# x-OSC_Gloves_v4_2.net
KiCad netlist of a schematic drawn in EAGLE
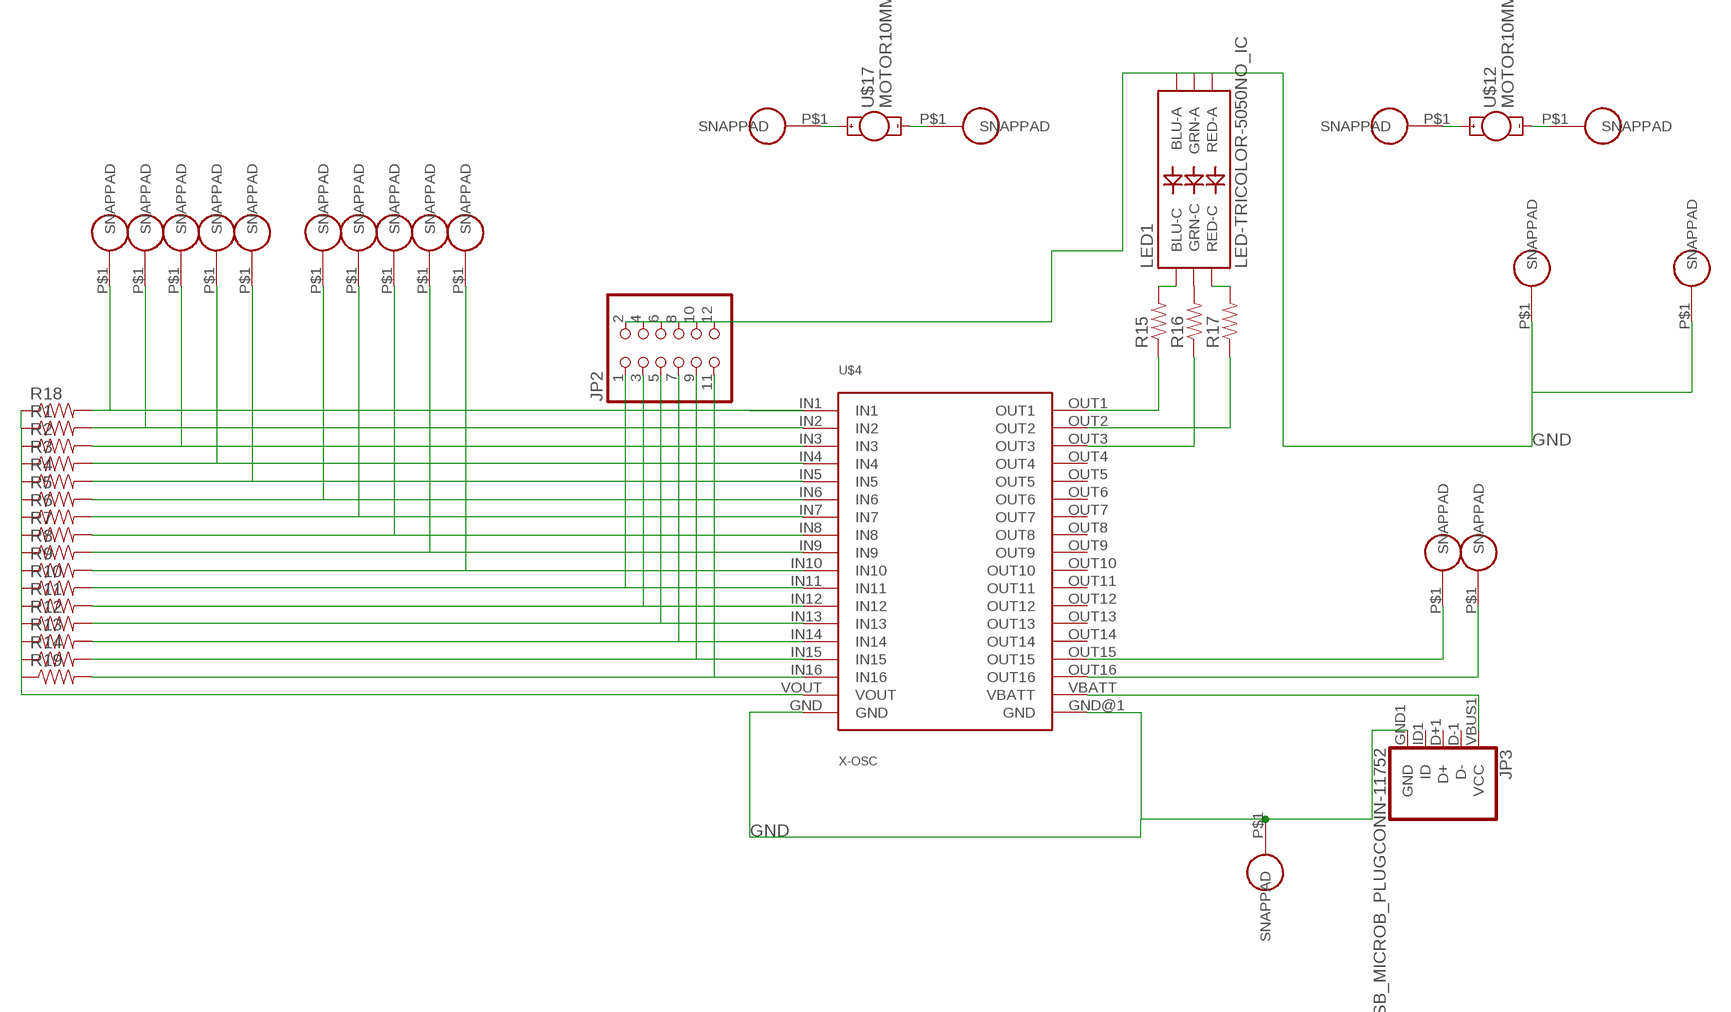
[diagram p0: schematic, sheet 1]

(export (version "E")
  (design (tool "Eeschema 10.0.6"))
  (components
    (comp (ref "JP2")
      (value "PINHD-2X6/90")
      (footprint "eagle-import:2X06_90")
      (libsource (lib "eagle-import") (part "PINHD-2X6/90"))
    )
    (comp (ref "JP3")
      (value "USB_MICROB_PLUGCONN-11752")
      (footprint "eagle-import:USB-B-MICRO-SMD_V03")
      (libsource (lib "eagle-import") (part "USB_MICROB_PLUGCONN-11752"))
    )
    (comp (ref "LED1")
      (value "LED-TRICOLOR-5050NO_IC")
      (footprint "eagle-import:LED-TRICOLOR-5050")
      (libsource (lib "eagle-import") (part "LED-TRICOLOR-5050NO_IC"))
    )
    (comp (ref "R1")
      (value "RESISTOR0805-RES")
      (footprint "eagle-import:0805")
      (libsource (lib "eagle-import") (part "RESISTOR0805-RES"))
    )
    (comp (ref "R2")
      (value "RESISTOR0805-RES")
      (footprint "eagle-import:0805")
      (libsource (lib "eagle-import") (part "RESISTOR0805-RES"))
    )
    (comp (ref "R3")
      (value "RESISTOR0805-RES")
      (footprint "eagle-import:0805")
      (libsource (lib "eagle-import") (part "RESISTOR0805-RES"))
    )
    (comp (ref "R4")
      (value "RESISTOR0805-RES")
      (footprint "eagle-import:0805")
      (libsource (lib "eagle-import") (part "RESISTOR0805-RES"))
    )
    (comp (ref "R5")
      (value "RESISTOR0805-RES")
      (footprint "eagle-import:0805")
      (libsource (lib "eagle-import") (part "RESISTOR0805-RES"))
    )
    (comp (ref "R6")
      (value "RESISTOR0805-RES")
      (footprint "eagle-import:0805")
      (libsource (lib "eagle-import") (part "RESISTOR0805-RES"))
    )
    (comp (ref "R7")
      (value "RESISTOR0805-RES")
      (footprint "eagle-import:0805")
      (libsource (lib "eagle-import") (part "RESISTOR0805-RES"))
    )
    (comp (ref "R8")
      (value "RESISTOR0805-RES")
      (footprint "eagle-import:0805")
      (libsource (lib "eagle-import") (part "RESISTOR0805-RES"))
    )
    (comp (ref "R9")
      (value "RESISTOR0805-RES")
      (footprint "eagle-import:0805")
      (libsource (lib "eagle-import") (part "RESISTOR0805-RES"))
    )
    (comp (ref "R10")
      (value "RESISTOR0805-RES")
      (footprint "eagle-import:0805")
      (libsource (lib "eagle-import") (part "RESISTOR0805-RES"))
    )
    (comp (ref "R11")
      (value "RESISTOR0805-RES")
      (footprint "eagle-import:0805")
      (libsource (lib "eagle-import") (part "RESISTOR0805-RES"))
    )
    (comp (ref "R12")
      (value "RESISTOR0805-RES")
      (footprint "eagle-import:0805")
      (libsource (lib "eagle-import") (part "RESISTOR0805-RES"))
    )
    (comp (ref "R13")
      (value "RESISTOR0805-RES")
      (footprint "eagle-import:0805")
      (libsource (lib "eagle-import") (part "RESISTOR0805-RES"))
    )
    (comp (ref "R14")
      (value "RESISTOR0805-RES")
      (footprint "eagle-import:0805")
      (libsource (lib "eagle-import") (part "RESISTOR0805-RES"))
    )
    (comp (ref "R15")
      (value "RESISTOR0805-RES")
      (footprint "eagle-import:0805")
      (libsource (lib "eagle-import") (part "RESISTOR0805-RES"))
    )
    (comp (ref "R16")
      (value "RESISTOR0805-RES")
      (footprint "eagle-import:0805")
      (libsource (lib "eagle-import") (part "RESISTOR0805-RES"))
    )
    (comp (ref "R17")
      (value "RESISTOR0805-RES")
      (footprint "eagle-import:0805")
      (libsource (lib "eagle-import") (part "RESISTOR0805-RES"))
    )
    (comp (ref "R18")
      (value "RESISTOR0805-RES")
      (footprint "eagle-import:0805")
      (libsource (lib "eagle-import") (part "RESISTOR0805-RES"))
    )
    (comp (ref "R19")
      (value "RESISTOR0805-RES")
      (footprint "eagle-import:0805")
      (libsource (lib "eagle-import") (part "RESISTOR0805-RES"))
    )
    (comp (ref "U$1")
      (value "SNAP-PAD_7MM_ROUND")
      (footprint "eagle-import:SNAP-PAD_7MM_RD")
      (libsource (lib "eagle-import") (part "SNAP-PAD_7MM_ROUND"))
    )
    (comp (ref "U$2")
      (value "SNAP-PAD_7MM_ROUND")
      (footprint "eagle-import:SNAP-PAD_7MM_RD")
      (libsource (lib "eagle-import") (part "SNAP-PAD_7MM_ROUND"))
    )
    (comp (ref "U$3")
      (value "SNAP-PAD_7MM_ROUND")
      (footprint "eagle-import:SNAP-PAD_7MM_RD")
      (libsource (lib "eagle-import") (part "SNAP-PAD_7MM_ROUND"))
    )
    (comp (ref "U$4")
      (value "X-OSC")
      (footprint "eagle-import:X-OSC_SMD")
      (libsource (lib "eagle-import") (part "X-OSC"))
    )
    (comp (ref "U$6")
      (value "SNAP-PAD_7MM_ROUND")
      (footprint "eagle-import:SNAP-PAD_7MM_RD")
      (libsource (lib "eagle-import") (part "SNAP-PAD_7MM_ROUND"))
    )
    (comp (ref "U$7")
      (value "SNAP-PAD_7MM_ROUND")
      (footprint "eagle-import:SNAP-PAD_7MM_RD")
      (libsource (lib "eagle-import") (part "SNAP-PAD_7MM_ROUND"))
    )
    (comp (ref "U$8")
      (value "SNAP-PAD_7MM_ROUND")
      (footprint "eagle-import:SNAP-PAD_7MM_RD")
      (libsource (lib "eagle-import") (part "SNAP-PAD_7MM_ROUND"))
    )
    (comp (ref "U$9")
      (value "SNAP-PAD_7MM_ROUND")
      (footprint "eagle-import:SNAP-PAD_7MM_RD")
      (libsource (lib "eagle-import") (part "SNAP-PAD_7MM_ROUND"))
    )
    (comp (ref "U$10")
      (value "SNAP-PAD_7MM_ROUND")
      (footprint "eagle-import:SNAP-PAD_7MM_RD")
      (libsource (lib "eagle-import") (part "SNAP-PAD_7MM_ROUND"))
    )
    (comp (ref "U$11")
      (value "SNAP-PAD_7MM_ROUND")
      (footprint "eagle-import:SNAP-PAD_7MM_RD")
      (libsource (lib "eagle-import") (part "SNAP-PAD_7MM_ROUND"))
    )
    (comp (ref "U$12")
      (value "MOTOR10MM")
      (footprint "eagle-import:VIBE-MOTOR-10MM")
      (libsource (lib "eagle-import") (part "MOTOR10MM"))
    )
    (comp (ref "U$13")
      (value "SNAP-PAD_7MM_ROUND")
      (footprint "eagle-import:SNAP-PAD_7MM_RD")
      (libsource (lib "eagle-import") (part "SNAP-PAD_7MM_ROUND"))
    )
    (comp (ref "U$14")
      (value "SNAP-PAD_7MM_ROUND")
      (footprint "eagle-import:SNAP-PAD_7MM_RD")
      (libsource (lib "eagle-import") (part "SNAP-PAD_7MM_ROUND"))
    )
    (comp (ref "U$15")
      (value "SNAP-PAD_7MM_ROUND")
      (footprint "eagle-import:SNAP-PAD_7MM_RD")
      (libsource (lib "eagle-import") (part "SNAP-PAD_7MM_ROUND"))
    )
    (comp (ref "U$16")
      (value "SNAP-PAD_7MM_ROUND")
      (footprint "eagle-import:SNAP-PAD_7MM_RD")
      (libsource (lib "eagle-import") (part "SNAP-PAD_7MM_ROUND"))
    )
    (comp (ref "U$17")
      (value "MOTOR10MM")
      (footprint "eagle-import:VIBE-MOTOR-10MM")
      (libsource (lib "eagle-import") (part "MOTOR10MM"))
    )
    (comp (ref "U$18")
      (value "SNAP-PAD_7MM_ROUND")
      (footprint "eagle-import:SNAP-PAD_7MM_RD")
      (libsource (lib "eagle-import") (part "SNAP-PAD_7MM_ROUND"))
    )
    (comp (ref "U$19")
      (value "SNAP-PAD_7MM_ROUND")
      (footprint "eagle-import:SNAP-PAD_7MM_RD")
      (libsource (lib "eagle-import") (part "SNAP-PAD_7MM_ROUND"))
    )
    (comp (ref "U$20")
      (value "SNAP-PAD_7MM_ROUND")
      (footprint "eagle-import:SNAP-PAD_7MM_RD")
      (libsource (lib "eagle-import") (part "SNAP-PAD_7MM_ROUND"))
    )
    (comp (ref "U$21")
      (value "SNAP-PAD_7MM_ROUND")
      (footprint "eagle-import:SNAP-PAD_7MM_RD")
      (libsource (lib "eagle-import") (part "SNAP-PAD_7MM_ROUND"))
    )
    (comp (ref "U$22")
      (value "SNAP-PAD_7MM_ROUND")
      (footprint "eagle-import:SNAP-PAD_7MM_RD")
      (libsource (lib "eagle-import") (part "SNAP-PAD_7MM_ROUND"))
    )
    (comp (ref "U$23")
      (value "SNAP-PAD_7MM_ROUND")
      (footprint "eagle-import:SNAP-PAD_7MM_RD")
      (libsource (lib "eagle-import") (part "SNAP-PAD_7MM_ROUND"))
    )
  )
  (nets
    (net (code "1") (name "/GND") (class "Default")
      (node (ref "JP2") (pin "10") (pinfunction "10_10") (pintype "passive"))
      (node (ref "JP2") (pin "12") (pinfunction "12_12") (pintype "passive"))
      (node (ref "JP2") (pin "2") (pinfunction "2_2") (pintype "passive"))
      (node (ref "JP2") (pin "4") (pinfunction "4_4") (pintype "passive"))
      (node (ref "JP2") (pin "6") (pinfunction "6_6") (pintype "passive"))
      (node (ref "JP2") (pin "8") (pinfunction "8_8") (pintype "passive"))
      (node (ref "JP3") (pin "GND1") (pinfunction "GND_GND1") (pintype "bidirectional"))
      (node (ref "LED1") (pin "1") (pinfunction "GRN-A_1") (pintype "bidirectional"))
      (node (ref "LED1") (pin "2") (pinfunction "RED-A_2") (pintype "bidirectional"))
      (node (ref "LED1") (pin "3") (pinfunction "BLU-A_3") (pintype "bidirectional"))
      (node (ref "U$15") (pin "P$1") (pinfunction "SNAPPAD_P$1") (pintype "bidirectional"))
      (node (ref "U$16") (pin "P$1") (pinfunction "SNAPPAD_P$1") (pintype "bidirectional"))
      (node (ref "U$18") (pin "P$1") (pinfunction "SNAPPAD_P$1") (pintype "bidirectional"))
      (node (ref "U$4") (pin "GND") (pinfunction "GND_GND") (pintype "bidirectional"))
      (node (ref "U$4") (pin "GND@1") (pinfunction "GND_GND@1") (pintype "bidirectional"))
    )
    (net (code "2") (name "Net-(JP2-Pad1)") (class "Default")
      (node (ref "JP2") (pin "1") (pinfunction "1_1") (pintype "passive"))
      (node (ref "R10") (pin "2") (pinfunction "2_2") (pintype "passive"))
      (node (ref "U$4") (pin "IN11") (pinfunction "IN11_IN11") (pintype "bidirectional"))
    )
    (net (code "3") (name "Net-(JP2-Pad3)") (class "Default")
      (node (ref "JP2") (pin "3") (pinfunction "3_3") (pintype "passive"))
      (node (ref "R11") (pin "2") (pinfunction "2_2") (pintype "passive"))
      (node (ref "U$4") (pin "IN12") (pinfunction "IN12_IN12") (pintype "bidirectional"))
    )
    (net (code "4") (name "Net-(JP2-Pad5)") (class "Default")
      (node (ref "JP2") (pin "5") (pinfunction "5_5") (pintype "passive"))
      (node (ref "R12") (pin "2") (pinfunction "2_2") (pintype "passive"))
      (node (ref "U$4") (pin "IN13") (pinfunction "IN13_IN13") (pintype "bidirectional"))
    )
    (net (code "5") (name "Net-(JP2-Pad7)") (class "Default")
      (node (ref "JP2") (pin "7") (pinfunction "7_7") (pintype "passive"))
      (node (ref "R13") (pin "2") (pinfunction "2_2") (pintype "passive"))
      (node (ref "U$4") (pin "IN14") (pinfunction "IN14_IN14") (pintype "bidirectional"))
    )
    (net (code "6") (name "Net-(JP2-Pad9)") (class "Default")
      (node (ref "JP2") (pin "9") (pinfunction "9_9") (pintype "passive"))
      (node (ref "R14") (pin "2") (pinfunction "2_2") (pintype "passive"))
      (node (ref "U$4") (pin "IN15") (pinfunction "IN15_IN15") (pintype "bidirectional"))
    )
    (net (code "7") (name "Net-(JP2-Pad11)") (class "Default")
      (node (ref "JP2") (pin "11") (pinfunction "11_11") (pintype "passive"))
      (node (ref "R19") (pin "2") (pinfunction "2_2") (pintype "passive"))
      (node (ref "U$4") (pin "IN16") (pinfunction "IN16_IN16") (pintype "bidirectional"))
    )
    (net (code "8") (name "Net-(JP3-VCC)") (class "Default")
      (node (ref "JP3") (pin "VBUS1") (pinfunction "VCC_VBUS1") (pintype "bidirectional"))
      (node (ref "U$4") (pin "VBATT") (pinfunction "VBATT_VBATT") (pintype "bidirectional"))
    )
    (net (code "9") (name "Net-(LED1-BLU-C)") (class "Default")
      (node (ref "LED1") (pin "4") (pinfunction "BLU-C_4") (pintype "bidirectional"))
      (node (ref "R15") (pin "2") (pinfunction "2_2") (pintype "passive"))
    )
    (net (code "10") (name "Net-(LED1-GRN-C)") (class "Default")
      (node (ref "LED1") (pin "6") (pinfunction "GRN-C_6") (pintype "bidirectional"))
      (node (ref "R16") (pin "2") (pinfunction "2_2") (pintype "passive"))
    )
    (net (code "11") (name "Net-(LED1-RED-C)") (class "Default")
      (node (ref "LED1") (pin "5") (pinfunction "RED-C_5") (pintype "bidirectional"))
      (node (ref "R17") (pin "2") (pinfunction "2_2") (pintype "passive"))
    )
    (net (code "12") (name "Net-(R1-Pad1)") (class "Default")
      (node (ref "R1") (pin "1") (pinfunction "1_1") (pintype "passive"))
      (node (ref "R10") (pin "1") (pinfunction "1_1") (pintype "passive"))
      (node (ref "R11") (pin "1") (pinfunction "1_1") (pintype "passive"))
      (node (ref "R12") (pin "1") (pinfunction "1_1") (pintype "passive"))
      (node (ref "R13") (pin "1") (pinfunction "1_1") (pintype "passive"))
      (node (ref "R14") (pin "1") (pinfunction "1_1") (pintype "passive"))
      (node (ref "R18") (pin "1") (pinfunction "1_1") (pintype "passive"))
      (node (ref "R19") (pin "1") (pinfunction "1_1") (pintype "passive"))
      (node (ref "R2") (pin "1") (pinfunction "1_1") (pintype "passive"))
      (node (ref "R3") (pin "1") (pinfunction "1_1") (pintype "passive"))
      (node (ref "R4") (pin "1") (pinfunction "1_1") (pintype "passive"))
      (node (ref "R5") (pin "1") (pinfunction "1_1") (pintype "passive"))
      (node (ref "R6") (pin "1") (pinfunction "1_1") (pintype "passive"))
      (node (ref "R7") (pin "1") (pinfunction "1_1") (pintype "passive"))
      (node (ref "R8") (pin "1") (pinfunction "1_1") (pintype "passive"))
      (node (ref "R9") (pin "1") (pinfunction "1_1") (pintype "passive"))
      (node (ref "U$4") (pin "VOUT") (pinfunction "VOUT_VOUT") (pintype "bidirectional"))
    )
    (net (code "13") (name "Net-(R15-Pad1)") (class "Default")
      (node (ref "R15") (pin "1") (pinfunction "1_1") (pintype "passive"))
      (node (ref "U$4") (pin "OUT1") (pinfunction "OUT1_OUT1") (pintype "bidirectional"))
    )
    (net (code "14") (name "Net-(R16-Pad1)") (class "Default")
      (node (ref "R16") (pin "1") (pinfunction "1_1") (pintype "passive"))
      (node (ref "U$4") (pin "OUT3") (pinfunction "OUT3_OUT3") (pintype "bidirectional"))
    )
    (net (code "15") (name "Net-(R17-Pad1)") (class "Default")
      (node (ref "R17") (pin "1") (pinfunction "1_1") (pintype "passive"))
      (node (ref "U$4") (pin "OUT2") (pinfunction "OUT2_OUT2") (pintype "bidirectional"))
    )
    (net (code "16") (name "Net-(U$1-SNAPPAD)") (class "Default")
      (node (ref "R1") (pin "2") (pinfunction "2_2") (pintype "passive"))
      (node (ref "U$1") (pin "P$1") (pinfunction "SNAPPAD_P$1") (pintype "bidirectional"))
      (node (ref "U$4") (pin "IN2") (pinfunction "IN2_IN2") (pintype "bidirectional"))
    )
    (net (code "17") (name "Net-(U$2-SNAPPAD)") (class "Default")
      (node (ref "R2") (pin "2") (pinfunction "2_2") (pintype "passive"))
      (node (ref "U$2") (pin "P$1") (pinfunction "SNAPPAD_P$1") (pintype "bidirectional"))
      (node (ref "U$4") (pin "IN3") (pinfunction "IN3_IN3") (pintype "bidirectional"))
    )
    (net (code "18") (name "Net-(U$3-SNAPPAD)") (class "Default")
      (node (ref "R3") (pin "2") (pinfunction "2_2") (pintype "passive"))
      (node (ref "U$3") (pin "P$1") (pinfunction "SNAPPAD_P$1") (pintype "bidirectional"))
      (node (ref "U$4") (pin "IN4") (pinfunction "IN4_IN4") (pintype "bidirectional"))
    )
    (net (code "19") (name "Net-(U$6-SNAPPAD)") (class "Default")
      (node (ref "R4") (pin "2") (pinfunction "2_2") (pintype "passive"))
      (node (ref "U$4") (pin "IN5") (pinfunction "IN5_IN5") (pintype "bidirectional"))
      (node (ref "U$6") (pin "P$1") (pinfunction "SNAPPAD_P$1") (pintype "bidirectional"))
    )
    (net (code "20") (name "Net-(U$7-SNAPPAD)") (class "Default")
      (node (ref "R5") (pin "2") (pinfunction "2_2") (pintype "passive"))
      (node (ref "U$4") (pin "IN6") (pinfunction "IN6_IN6") (pintype "bidirectional"))
      (node (ref "U$7") (pin "P$1") (pinfunction "SNAPPAD_P$1") (pintype "bidirectional"))
    )
    (net (code "21") (name "Net-(U$8-SNAPPAD)") (class "Default")
      (node (ref "R6") (pin "2") (pinfunction "2_2") (pintype "passive"))
      (node (ref "U$4") (pin "IN7") (pinfunction "IN7_IN7") (pintype "bidirectional"))
      (node (ref "U$8") (pin "P$1") (pinfunction "SNAPPAD_P$1") (pintype "bidirectional"))
    )
    (net (code "22") (name "Net-(U$9-SNAPPAD)") (class "Default")
      (node (ref "R7") (pin "2") (pinfunction "2_2") (pintype "passive"))
      (node (ref "U$4") (pin "IN8") (pinfunction "IN8_IN8") (pintype "bidirectional"))
      (node (ref "U$9") (pin "P$1") (pinfunction "SNAPPAD_P$1") (pintype "bidirectional"))
    )
    (net (code "23") (name "Net-(U$10-SNAPPAD)") (class "Default")
      (node (ref "R8") (pin "2") (pinfunction "2_2") (pintype "passive"))
      (node (ref "U$10") (pin "P$1") (pinfunction "SNAPPAD_P$1") (pintype "bidirectional"))
      (node (ref "U$4") (pin "IN9") (pinfunction "IN9_IN9") (pintype "bidirectional"))
    )
    (net (code "24") (name "Net-(U$11-SNAPPAD)") (class "Default")
      (node (ref "R9") (pin "2") (pinfunction "2_2") (pintype "passive"))
      (node (ref "U$11") (pin "P$1") (pinfunction "SNAPPAD_P$1") (pintype "bidirectional"))
      (node (ref "U$4") (pin "IN10") (pinfunction "IN10_IN10") (pintype "bidirectional"))
    )
    (net (code "25") (name "Net-(U$13-SNAPPAD)") (class "Default")
      (node (ref "U$13") (pin "P$1") (pinfunction "SNAPPAD_P$1") (pintype "bidirectional"))
      (node (ref "U$4") (pin "OUT15") (pinfunction "OUT15_OUT15") (pintype "bidirectional"))
    )
    (net (code "26") (name "Net-(U$14-SNAPPAD)") (class "Default")
      (node (ref "U$14") (pin "P$1") (pinfunction "SNAPPAD_P$1") (pintype "bidirectional"))
      (node (ref "U$4") (pin "OUT16") (pinfunction "OUT16_OUT16") (pintype "bidirectional"))
    )
    (net (code "27") (name "Net-(U$19-SNAPPAD)") (class "Default")
      (node (ref "U$17") (pin "+") (pinfunction "+_+") (pintype "bidirectional"))
      (node (ref "U$19") (pin "P$1") (pinfunction "SNAPPAD_P$1") (pintype "bidirectional"))
    )
    (net (code "28") (name "Net-(U$20-SNAPPAD)") (class "Default")
      (node (ref "U$17") (pin "-") (pinfunction "-_-") (pintype "bidirectional"))
      (node (ref "U$20") (pin "P$1") (pinfunction "SNAPPAD_P$1") (pintype "bidirectional"))
    )
    (net (code "29") (name "Net-(U$21-SNAPPAD)") (class "Default")
      (node (ref "R18") (pin "2") (pinfunction "2_2") (pintype "passive"))
      (node (ref "U$21") (pin "P$1") (pinfunction "SNAPPAD_P$1") (pintype "bidirectional"))
      (node (ref "U$4") (pin "IN1") (pinfunction "IN1_IN1") (pintype "bidirectional"))
    )
    (net (code "30") (name "Net-(U$22-SNAPPAD)") (class "Default")
      (node (ref "U$12") (pin "+") (pinfunction "+_+") (pintype "bidirectional"))
      (node (ref "U$22") (pin "P$1") (pinfunction "SNAPPAD_P$1") (pintype "bidirectional"))
    )
    (net (code "31") (name "Net-(U$23-SNAPPAD)") (class "Default")
      (node (ref "U$12") (pin "-") (pinfunction "-_-") (pintype "bidirectional"))
      (node (ref "U$23") (pin "P$1") (pinfunction "SNAPPAD_P$1") (pintype "bidirectional"))
    )
    (net (code "32") (name "unconnected-(JP3-D+-PadD+1)") (class "Default")
      (node (ref "JP3") (pin "D+1") (pinfunction "D+_D+1") (pintype "bidirectional"))
    )
    (net (code "33") (name "unconnected-(JP3-D--PadD-1)") (class "Default")
      (node (ref "JP3") (pin "D-1") (pinfunction "D-_D-1") (pintype "bidirectional"))
    )
    (net (code "34") (name "unconnected-(JP3-ID-PadID1)") (class "Default")
      (node (ref "JP3") (pin "ID1") (pinfunction "ID_ID1") (pintype "bidirectional"))
    )
    (net (code "35") (name "unconnected-(U$4-PadOUT4)") (class "Default")
      (node (ref "U$4") (pin "OUT4") (pinfunction "OUT4_OUT4") (pintype "bidirectional"))
    )
    (net (code "36") (name "unconnected-(U$4-PadOUT5)") (class "Default")
      (node (ref "U$4") (pin "OUT5") (pinfunction "OUT5_OUT5") (pintype "bidirectional"))
    )
    (net (code "37") (name "unconnected-(U$4-PadOUT6)") (class "Default")
      (node (ref "U$4") (pin "OUT6") (pinfunction "OUT6_OUT6") (pintype "bidirectional"))
    )
    (net (code "38") (name "unconnected-(U$4-PadOUT7)") (class "Default")
      (node (ref "U$4") (pin "OUT7") (pinfunction "OUT7_OUT7") (pintype "bidirectional"))
    )
    (net (code "39") (name "unconnected-(U$4-PadOUT8)") (class "Default")
      (node (ref "U$4") (pin "OUT8") (pinfunction "OUT8_OUT8") (pintype "bidirectional"))
    )
    (net (code "40") (name "unconnected-(U$4-PadOUT9)") (class "Default")
      (node (ref "U$4") (pin "OUT9") (pinfunction "OUT9_OUT9") (pintype "bidirectional"))
    )
    (net (code "41") (name "unconnected-(U$4-PadOUT10)") (class "Default")
      (node (ref "U$4") (pin "OUT10") (pinfunction "OUT10_OUT10") (pintype "bidirectional"))
    )
    (net (code "42") (name "unconnected-(U$4-PadOUT11)") (class "Default")
      (node (ref "U$4") (pin "OUT11") (pinfunction "OUT11_OUT11") (pintype "bidirectional"))
    )
    (net (code "43") (name "unconnected-(U$4-PadOUT12)") (class "Default")
      (node (ref "U$4") (pin "OUT12") (pinfunction "OUT12_OUT12") (pintype "bidirectional"))
    )
    (net (code "44") (name "unconnected-(U$4-PadOUT13)") (class "Default")
      (node (ref "U$4") (pin "OUT13") (pinfunction "OUT13_OUT13") (pintype "bidirectional"))
    )
    (net (code "45") (name "unconnected-(U$4-PadOUT14)") (class "Default")
      (node (ref "U$4") (pin "OUT14") (pinfunction "OUT14_OUT14") (pintype "bidirectional"))
    )
  )
)
